# megabit-I2C-TOP.net
KiCad netlist of a schematic drawn in Altium Designer
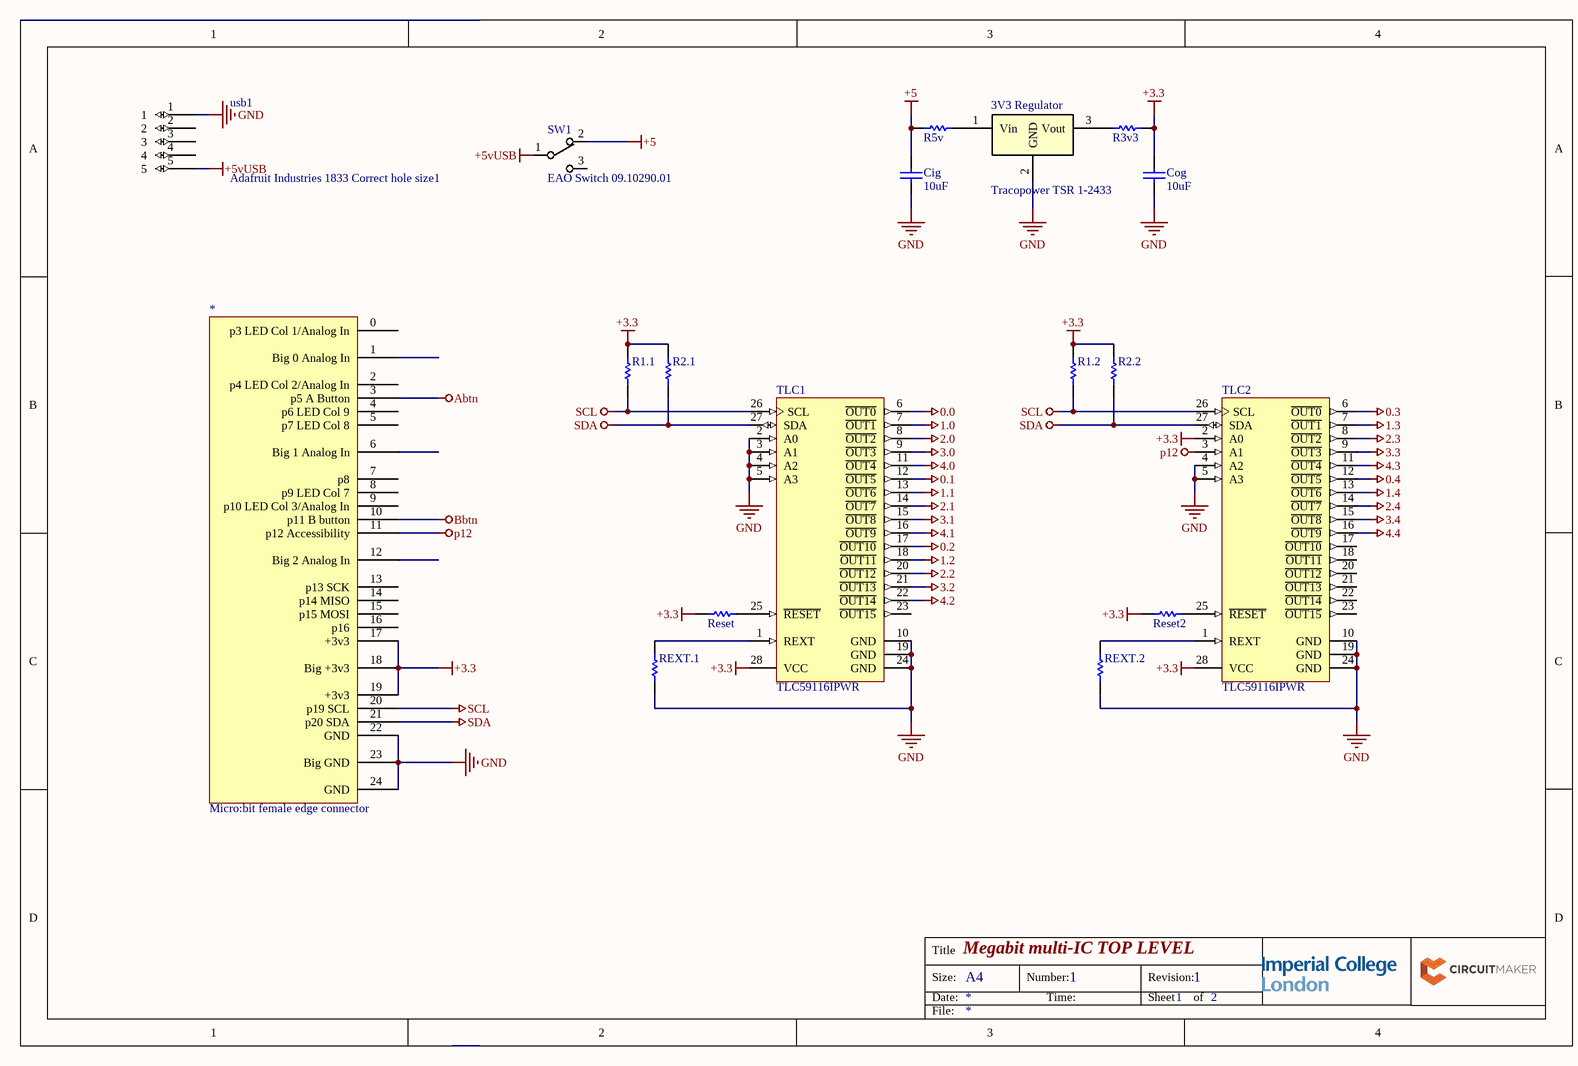
[diagram p0: megabit-I2C-TOP.SchDoc]

(export (version "E")
  (design (tool "Eeschema 10.0.6"))
  (components
    (comp (ref "*")
      (value "Micro:bit female edge connector")
      (footprint "PCBComponent_1 - duplicate")
      (description "http://www.dgyuliang.net/html/279.html")
      (libsource (lib "CommunityVault") (part "SYM-mom7rix79jkpy4z4w6go-1"))
    )
    (comp (ref "3V3 Regulator")
      (value "Tracopower TSR 1-2433")
      (footprint "PCB-vczw4772xz5kvcrv4x78-1")
      (description "1 A Watt, 4.75-36VDCVin, Quad Output, 3.3 V@1 A Switching Regulators DC-DC Converter")
      (fields (field (name "MANUFACTURER PART NUMBER") "TSR 1-2433"))
      (libsource (lib "CommunityVault") (part "SYM-395cf0c79334e69b-1"))
    )
    (comp (ref "Cig")
      (value "10uF")
      (footprint "Vishay K104K15X7RF5TL2")
      (description "K Series 100nF 50 V ±10 % Tolerance X7R Radial Multilayer Ceramic Capacitor")
      (fields (field (name "MANUFACTURER PART NUMBER") "K104K15X7RF5TL2"))
      (libsource (lib "CommunityVault") (part "CMP-124240-16"))
    )
    (comp (ref "Cog")
      (value "10uF")
      (footprint "Vishay K104K15X7RF5TL2")
      (description "K Series 100nF 50 V ±10 % Tolerance X7R Radial Multilayer Ceramic Capacitor")
      (fields (field (name "MANUFACTURER PART NUMBER") "K104K15X7RF5TL2"))
      (libsource (lib "CommunityVault") (part "CMP-124240-16"))
    )
    (comp (ref "R1.1")
      (value "Res1")
      (footprint "PCB-3613466-1")
      (description "Resistor 0.25W")
      (libsource (lib "CommunityVault") (part "CMP-b15c796618a36e9b-3"))
    )
    (comp (ref "R1.2")
      (value "Res1")
      (footprint "PCB-3613466-1")
      (description "Resistor 0.25W")
      (libsource (lib "CommunityVault") (part "CMP-b15c796618a36e9b-3"))
    )
    (comp (ref "R2.1")
      (value "Res1")
      (footprint "PCB-3613466-1")
      (description "Resistor 0.25W")
      (libsource (lib "CommunityVault") (part "CMP-b15c796618a36e9b-3"))
    )
    (comp (ref "R2.2")
      (value "Res1")
      (footprint "PCB-3613466-1")
      (description "Resistor 0.25W")
      (libsource (lib "CommunityVault") (part "CMP-b15c796618a36e9b-3"))
    )
    (comp (ref "R3v3")
      (value "Res1")
      (footprint "PCB-3613466-1")
      (description "Resistor 0.25W")
      (libsource (lib "CommunityVault") (part "CMP-b15c796618a36e9b-3"))
    )
    (comp (ref "R5v")
      (value "Res1")
      (footprint "PCB-3613466-1")
      (description "Resistor 0.25W")
      (libsource (lib "CommunityVault") (part "CMP-b15c796618a36e9b-3"))
    )
    (comp (ref "Reset")
      (value "Res1")
      (footprint "PCB-3613466-1")
      (description "Resistor 0.25W")
      (libsource (lib "CommunityVault") (part "CMP-b15c796618a36e9b-3"))
    )
    (comp (ref "Reset2")
      (value "Res1")
      (footprint "PCB-3613466-1")
      (description "Resistor 0.25W")
      (libsource (lib "CommunityVault") (part "CMP-b15c796618a36e9b-3"))
    )
    (comp (ref "REXT.1")
      (value "R-EXT")
      (footprint "PCB-3613466-1")
      (description "Resistor 0.25W")
      (libsource (lib "CommunityVault") (part "CMP-b15c796618a36e9b-3"))
    )
    (comp (ref "REXT.2")
      (value "R-EXT")
      (footprint "PCB-3613466-1")
      (description "Resistor 0.25W")
      (libsource (lib "CommunityVault") (part "CMP-b15c796618a36e9b-3"))
    )
    (comp (ref "SW1")
      (value "EAO Switch 09.10290.01")
      (footprint "PCB-1akl86m7w5ikau1ha4dm-1")
      (fields (field (name "MANUFACTURER PART NUMBER") "09.10290.01"))
      (libsource (lib "CommunityVault") (part "CMP-a30d6b12014b7cca-5"))
    )
    (comp (ref "TLC1")
      (value "TLC59116IPWR")
      (footprint "TI-PW28_L")
      (libsource (lib "CommunityVault") (part "CMP-1160291-2"))
    )
    (comp (ref "TLC2")
      (value "TLC59116IPWR")
      (footprint "TI-PW28_L")
      (libsource (lib "CommunityVault") (part "CMP-1160291-2"))
    )
    (comp (ref "usb1")
      (value "Adafruit Industries 1833 Correct hole size1")
      (footprint "PCB-lrx1ysvqy1j2hi3n37c6-1")
      (description "Standoff; Threaded Female 1/4 Hex; 6-32 Thread; Length .875; Brass/Zinc")
      (fields (field (name "MANUFACTURER PART NUMBER") "1833"))
      (libsource (lib "FavoritesLibrary") (part "SYM-bfb17591a6f36076-1"))
    )
  )
  (nets
    (net (code "1") (name "+3.3") (class "Default")
      (node (ref "*") (pin "17") (pinfunction "+3v3_17") (pintype "passive"))
      (node (ref "*") (pin "18") (pinfunction "Big_+3v3_18") (pintype "passive"))
      (node (ref "*") (pin "19") (pinfunction "+3v3_19") (pintype "passive"))
      (node (ref "Cog") (pin "2") (pinfunction "2_2") (pintype "passive"))
      (node (ref "R1.1") (pin "2") (pinfunction "2_2") (pintype "passive"))
      (node (ref "R1.2") (pin "2") (pinfunction "2_2") (pintype "passive"))
      (node (ref "R2.1") (pin "2") (pinfunction "2_2") (pintype "passive"))
      (node (ref "R2.2") (pin "2") (pinfunction "2_2") (pintype "passive"))
      (node (ref "R3v3") (pin "2") (pinfunction "2_2") (pintype "passive"))
      (node (ref "Reset") (pin "1") (pinfunction "1_1") (pintype "passive"))
      (node (ref "Reset2") (pin "1") (pinfunction "1_1") (pintype "passive"))
      (node (ref "TLC1") (pin "28") (pinfunction "VCC_28") (pintype "power_in"))
      (node (ref "TLC2") (pin "2") (pinfunction "A0_2") (pintype "input"))
      (node (ref "TLC2") (pin "28") (pinfunction "VCC_28") (pintype "power_in"))
    )
    (net (code "2") (name "+5") (class "Default")
      (node (ref "Cig") (pin "2") (pinfunction "2_2") (pintype "passive"))
      (node (ref "R5v") (pin "1") (pinfunction "1_1") (pintype "passive"))
      (node (ref "SW1") (pin "2") (pinfunction "2_2") (pintype "passive"))
    )
    (net (code "3") (name "+5vUSB") (class "Default")
      (node (ref "SW1") (pin "1") (pinfunction "1_1") (pintype "passive"))
      (node (ref "usb1") (pin "5") (pinfunction "5_5") (pintype "bidirectional"))
    )
    (net (code "4") (name "0.0") (class "Default")
      (node (ref "TLC1") (pin "6") (pinfunction "~{OUT0}_6") (pintype "output"))
    )
    (net (code "5") (name "0.1") (class "Default")
      (node (ref "TLC1") (pin "12") (pinfunction "~{OUT5}_12") (pintype "output"))
    )
    (net (code "6") (name "0.2") (class "Default")
      (node (ref "TLC1") (pin "17") (pinfunction "~{OUT10}_17") (pintype "output"))
    )
    (net (code "7") (name "0.3") (class "Default")
      (node (ref "TLC2") (pin "6") (pinfunction "~{OUT0}_6") (pintype "output"))
    )
    (net (code "8") (name "0.4") (class "Default")
      (node (ref "TLC2") (pin "12") (pinfunction "~{OUT5}_12") (pintype "output"))
    )
    (net (code "9") (name "1.0") (class "Default")
      (node (ref "TLC1") (pin "7") (pinfunction "~{OUT1}_7") (pintype "output"))
    )
    (net (code "10") (name "1.1") (class "Default")
      (node (ref "TLC1") (pin "13") (pinfunction "~{OUT6}_13") (pintype "output"))
    )
    (net (code "11") (name "1.2") (class "Default")
      (node (ref "TLC1") (pin "18") (pinfunction "~{OUT11}_18") (pintype "output"))
    )
    (net (code "12") (name "1.3") (class "Default")
      (node (ref "TLC2") (pin "7") (pinfunction "~{OUT1}_7") (pintype "output"))
    )
    (net (code "13") (name "1.4") (class "Default")
      (node (ref "TLC2") (pin "13") (pinfunction "~{OUT6}_13") (pintype "output"))
    )
    (net (code "14") (name "2.0") (class "Default")
      (node (ref "TLC1") (pin "8") (pinfunction "~{OUT2}_8") (pintype "output"))
    )
    (net (code "15") (name "2.1") (class "Default")
      (node (ref "TLC1") (pin "14") (pinfunction "~{OUT7}_14") (pintype "output"))
    )
    (net (code "16") (name "2.2") (class "Default")
      (node (ref "TLC1") (pin "20") (pinfunction "~{OUT12}_20") (pintype "output"))
    )
    (net (code "17") (name "2.3") (class "Default")
      (node (ref "TLC2") (pin "8") (pinfunction "~{OUT2}_8") (pintype "output"))
    )
    (net (code "18") (name "2.4") (class "Default")
      (node (ref "TLC2") (pin "14") (pinfunction "~{OUT7}_14") (pintype "output"))
    )
    (net (code "19") (name "3.0") (class "Default")
      (node (ref "TLC1") (pin "9") (pinfunction "~{OUT3}_9") (pintype "output"))
    )
    (net (code "20") (name "3.1") (class "Default")
      (node (ref "TLC1") (pin "15") (pinfunction "~{OUT8}_15") (pintype "output"))
    )
    (net (code "21") (name "3.2") (class "Default")
      (node (ref "TLC1") (pin "21") (pinfunction "~{OUT13}_21") (pintype "output"))
    )
    (net (code "22") (name "3.3") (class "Default")
      (node (ref "TLC2") (pin "9") (pinfunction "~{OUT3}_9") (pintype "output"))
    )
    (net (code "23") (name "3.4") (class "Default")
      (node (ref "TLC2") (pin "15") (pinfunction "~{OUT8}_15") (pintype "output"))
    )
    (net (code "24") (name "4.0") (class "Default")
      (node (ref "TLC1") (pin "11") (pinfunction "~{OUT4}_11") (pintype "output"))
    )
    (net (code "25") (name "4.1") (class "Default")
      (node (ref "TLC1") (pin "16") (pinfunction "~{OUT9}_16") (pintype "output"))
    )
    (net (code "26") (name "4.2") (class "Default")
      (node (ref "TLC1") (pin "22") (pinfunction "~{OUT14}_22") (pintype "output"))
    )
    (net (code "27") (name "4.3") (class "Default")
      (node (ref "TLC2") (pin "11") (pinfunction "~{OUT4}_11") (pintype "output"))
    )
    (net (code "28") (name "4.4") (class "Default")
      (node (ref "TLC2") (pin "16") (pinfunction "~{OUT9}_16") (pintype "output"))
    )
    (net (code "29") (name "Abtn") (class "Default")
      (node (ref "*") (pin "3") (pinfunction "p5_A_Button_3") (pintype "passive"))
    )
    (net (code "30") (name "Bbtn") (class "Default")
      (node (ref "*") (pin "10") (pinfunction "p11_B_button_10") (pintype "passive"))
    )
    (net (code "31") (name "GND") (class "Default")
      (node (ref "*") (pin "22") (pinfunction "GND_22") (pintype "passive"))
      (node (ref "*") (pin "23") (pinfunction "Big_GND_23") (pintype "passive"))
      (node (ref "*") (pin "24") (pinfunction "GND_24") (pintype "passive"))
      (node (ref "3V3 Regulator") (pin "2") (pinfunction "GND_2") (pintype "power_in"))
      (node (ref "Cig") (pin "1") (pinfunction "1_1") (pintype "passive"))
      (node (ref "Cog") (pin "1") (pinfunction "1_1") (pintype "passive"))
      (node (ref "REXT.1") (pin "1") (pinfunction "1_1") (pintype "passive"))
      (node (ref "REXT.2") (pin "1") (pinfunction "1_1") (pintype "passive"))
      (node (ref "TLC1") (pin "10") (pinfunction "GND_10") (pintype "power_in"))
      (node (ref "TLC1") (pin "19") (pinfunction "GND_19") (pintype "power_in"))
      (node (ref "TLC1") (pin "2") (pinfunction "A0_2") (pintype "input"))
      (node (ref "TLC1") (pin "24") (pinfunction "GND_24") (pintype "power_in"))
      (node (ref "TLC1") (pin "3") (pinfunction "A1_3") (pintype "input"))
      (node (ref "TLC1") (pin "4") (pinfunction "A2_4") (pintype "input"))
      (node (ref "TLC1") (pin "5") (pinfunction "A3_5") (pintype "input"))
      (node (ref "TLC2") (pin "10") (pinfunction "GND_10") (pintype "power_in"))
      (node (ref "TLC2") (pin "19") (pinfunction "GND_19") (pintype "power_in"))
      (node (ref "TLC2") (pin "24") (pinfunction "GND_24") (pintype "power_in"))
      (node (ref "TLC2") (pin "4") (pinfunction "A2_4") (pintype "input"))
      (node (ref "TLC2") (pin "5") (pinfunction "A3_5") (pintype "input"))
      (node (ref "usb1") (pin "1") (pinfunction "1_1") (pintype "bidirectional"))
    )
    (net (code "32") (name "Net-(3V3 Regulator-Vin)") (class "Default")
      (node (ref "3V3 Regulator") (pin "1") (pinfunction "Vin_1") (pintype "power_in"))
      (node (ref "R5v") (pin "2") (pinfunction "2_2") (pintype "passive"))
    )
    (net (code "33") (name "Net-(3V3 Regulator-Vout)") (class "Default")
      (node (ref "3V3 Regulator") (pin "3") (pinfunction "Vout_3") (pintype "power_in"))
      (node (ref "R3v3") (pin "1") (pinfunction "1_1") (pintype "passive"))
    )
    (net (code "34") (name "Net-(TLC1-REXT)") (class "Default")
      (node (ref "REXT.1") (pin "2") (pinfunction "2_2") (pintype "passive"))
      (node (ref "TLC1") (pin "1") (pinfunction "REXT_1") (pintype "input"))
    )
    (net (code "35") (name "Net-(TLC1-~{RESET})") (class "Default")
      (node (ref "Reset") (pin "2") (pinfunction "2_2") (pintype "passive"))
      (node (ref "TLC1") (pin "25") (pinfunction "~{RESET}_25") (pintype "input"))
    )
    (net (code "36") (name "Net-(TLC2-REXT)") (class "Default")
      (node (ref "REXT.2") (pin "2") (pinfunction "2_2") (pintype "passive"))
      (node (ref "TLC2") (pin "1") (pinfunction "REXT_1") (pintype "input"))
    )
    (net (code "37") (name "Net-(TLC2-~{RESET})") (class "Default")
      (node (ref "Reset2") (pin "2") (pinfunction "2_2") (pintype "passive"))
      (node (ref "TLC2") (pin "25") (pinfunction "~{RESET}_25") (pintype "input"))
    )
    (net (code "38") (name "SCL") (class "Default")
      (node (ref "*") (pin "20") (pinfunction "p19_SCL_20") (pintype "passive"))
      (node (ref "R1.1") (pin "1") (pinfunction "1_1") (pintype "passive"))
      (node (ref "R1.2") (pin "1") (pinfunction "1_1") (pintype "passive"))
      (node (ref "TLC1") (pin "26") (pinfunction "SCL_26") (pintype "input"))
      (node (ref "TLC2") (pin "26") (pinfunction "SCL_26") (pintype "input"))
    )
    (net (code "39") (name "SDA") (class "Default")
      (node (ref "*") (pin "21") (pinfunction "p20_SDA_21") (pintype "passive"))
      (node (ref "R2.1") (pin "1") (pinfunction "1_1") (pintype "passive"))
      (node (ref "R2.2") (pin "1") (pinfunction "1_1") (pintype "passive"))
      (node (ref "TLC1") (pin "27") (pinfunction "SDA_27") (pintype "bidirectional"))
      (node (ref "TLC2") (pin "27") (pinfunction "SDA_27") (pintype "bidirectional"))
    )
    (net (code "40") (name "p12") (class "Default")
      (node (ref "*") (pin "11") (pinfunction "p12_Accessibility_11") (pintype "passive"))
      (node (ref "TLC2") (pin "3") (pinfunction "A1_3") (pintype "input"))
    )
    (net (code "41") (name "unconnected-(*-Big_0_Analog_In-Pad1)") (class "Default")
      (node (ref "*") (pin "1") (pinfunction "Big_0_Analog_In_1") (pintype "passive"))
    )
    (net (code "42") (name "unconnected-(*-Big_1_Analog_In-Pad6)") (class "Default")
      (node (ref "*") (pin "6") (pinfunction "Big_1_Analog_In_6") (pintype "passive"))
    )
    (net (code "43") (name "unconnected-(*-Big_2_Analog_In-Pad12)") (class "Default")
      (node (ref "*") (pin "12") (pinfunction "Big_2_Analog_In_12") (pintype "passive"))
    )
    (net (code "44") (name "unconnected-(*-p3_LED_Col_1{slash}Analog_In-Pad0)") (class "Default")
      (node (ref "*") (pin "0") (pinfunction "p3_LED_Col_1/Analog_In_0") (pintype "passive"))
    )
    (net (code "45") (name "unconnected-(*-p4_LED_Col_2{slash}Analog_In-Pad2)") (class "Default")
      (node (ref "*") (pin "2") (pinfunction "p4_LED_Col_2/Analog_In_2") (pintype "passive"))
    )
    (net (code "46") (name "unconnected-(*-p6_LED_Col_9-Pad4)") (class "Default")
      (node (ref "*") (pin "4") (pinfunction "p6_LED_Col_9_4") (pintype "passive"))
    )
    (net (code "47") (name "unconnected-(*-p7_LED_Col_8-Pad5)") (class "Default")
      (node (ref "*") (pin "5") (pinfunction "p7_LED_Col_8_5") (pintype "passive"))
    )
    (net (code "48") (name "unconnected-(*-p8-Pad7)") (class "Default")
      (node (ref "*") (pin "7") (pinfunction "p8_7") (pintype "passive"))
    )
    (net (code "49") (name "unconnected-(*-p9_LED_Col_7-Pad8)") (class "Default")
      (node (ref "*") (pin "8") (pinfunction "p9_LED_Col_7_8") (pintype "passive"))
    )
    (net (code "50") (name "unconnected-(*-p10_LED_Col_3{slash}Analog_In-Pad9)") (class "Default")
      (node (ref "*") (pin "9") (pinfunction "p10_LED_Col_3/Analog_In_9") (pintype "passive"))
    )
    (net (code "51") (name "unconnected-(*-p13_SCK-Pad13)") (class "Default")
      (node (ref "*") (pin "13") (pinfunction "p13_SCK_13") (pintype "passive"))
    )
    (net (code "52") (name "unconnected-(*-p14_MISO-Pad14)") (class "Default")
      (node (ref "*") (pin "14") (pinfunction "p14_MISO_14") (pintype "passive"))
    )
    (net (code "53") (name "unconnected-(*-p15_MOSI-Pad15)") (class "Default")
      (node (ref "*") (pin "15") (pinfunction "p15_MOSI_15") (pintype "passive"))
    )
    (net (code "54") (name "unconnected-(*-p16-Pad16)") (class "Default")
      (node (ref "*") (pin "16") (pinfunction "p16_16") (pintype "passive"))
    )
    (net (code "55") (name "unconnected-(SW1-Pad3)") (class "Default")
      (node (ref "SW1") (pin "3") (pinfunction "3_3") (pintype "passive"))
    )
    (net (code "56") (name "unconnected-(TLC1-~{OUT15}-Pad23)") (class "Default")
      (node (ref "TLC1") (pin "23") (pinfunction "~{OUT15}_23") (pintype "output"))
    )
    (net (code "57") (name "unconnected-(TLC2-~{OUT10}-Pad17)") (class "Default")
      (node (ref "TLC2") (pin "17") (pinfunction "~{OUT10}_17") (pintype "output"))
    )
    (net (code "58") (name "unconnected-(TLC2-~{OUT11}-Pad18)") (class "Default")
      (node (ref "TLC2") (pin "18") (pinfunction "~{OUT11}_18") (pintype "output"))
    )
    (net (code "59") (name "unconnected-(TLC2-~{OUT12}-Pad20)") (class "Default")
      (node (ref "TLC2") (pin "20") (pinfunction "~{OUT12}_20") (pintype "output"))
    )
    (net (code "60") (name "unconnected-(TLC2-~{OUT13}-Pad21)") (class "Default")
      (node (ref "TLC2") (pin "21") (pinfunction "~{OUT13}_21") (pintype "output"))
    )
    (net (code "61") (name "unconnected-(TLC2-~{OUT14}-Pad22)") (class "Default")
      (node (ref "TLC2") (pin "22") (pinfunction "~{OUT14}_22") (pintype "output"))
    )
    (net (code "62") (name "unconnected-(TLC2-~{OUT15}-Pad23)") (class "Default")
      (node (ref "TLC2") (pin "23") (pinfunction "~{OUT15}_23") (pintype "output"))
    )
    (net (code "63") (name "unconnected-(usb1-Pad2)") (class "Default")
      (node (ref "usb1") (pin "2") (pinfunction "2_2") (pintype "bidirectional"))
    )
    (net (code "64") (name "unconnected-(usb1-Pad3)") (class "Default")
      (node (ref "usb1") (pin "3") (pinfunction "3_3") (pintype "bidirectional"))
    )
    (net (code "65") (name "unconnected-(usb1-Pad4)") (class "Default")
      (node (ref "usb1") (pin "4") (pinfunction "4_4") (pintype "bidirectional"))
    )
  )
)
